# eVV_Sensors.net
KiCad netlist of a schematic drawn in Altium Designer
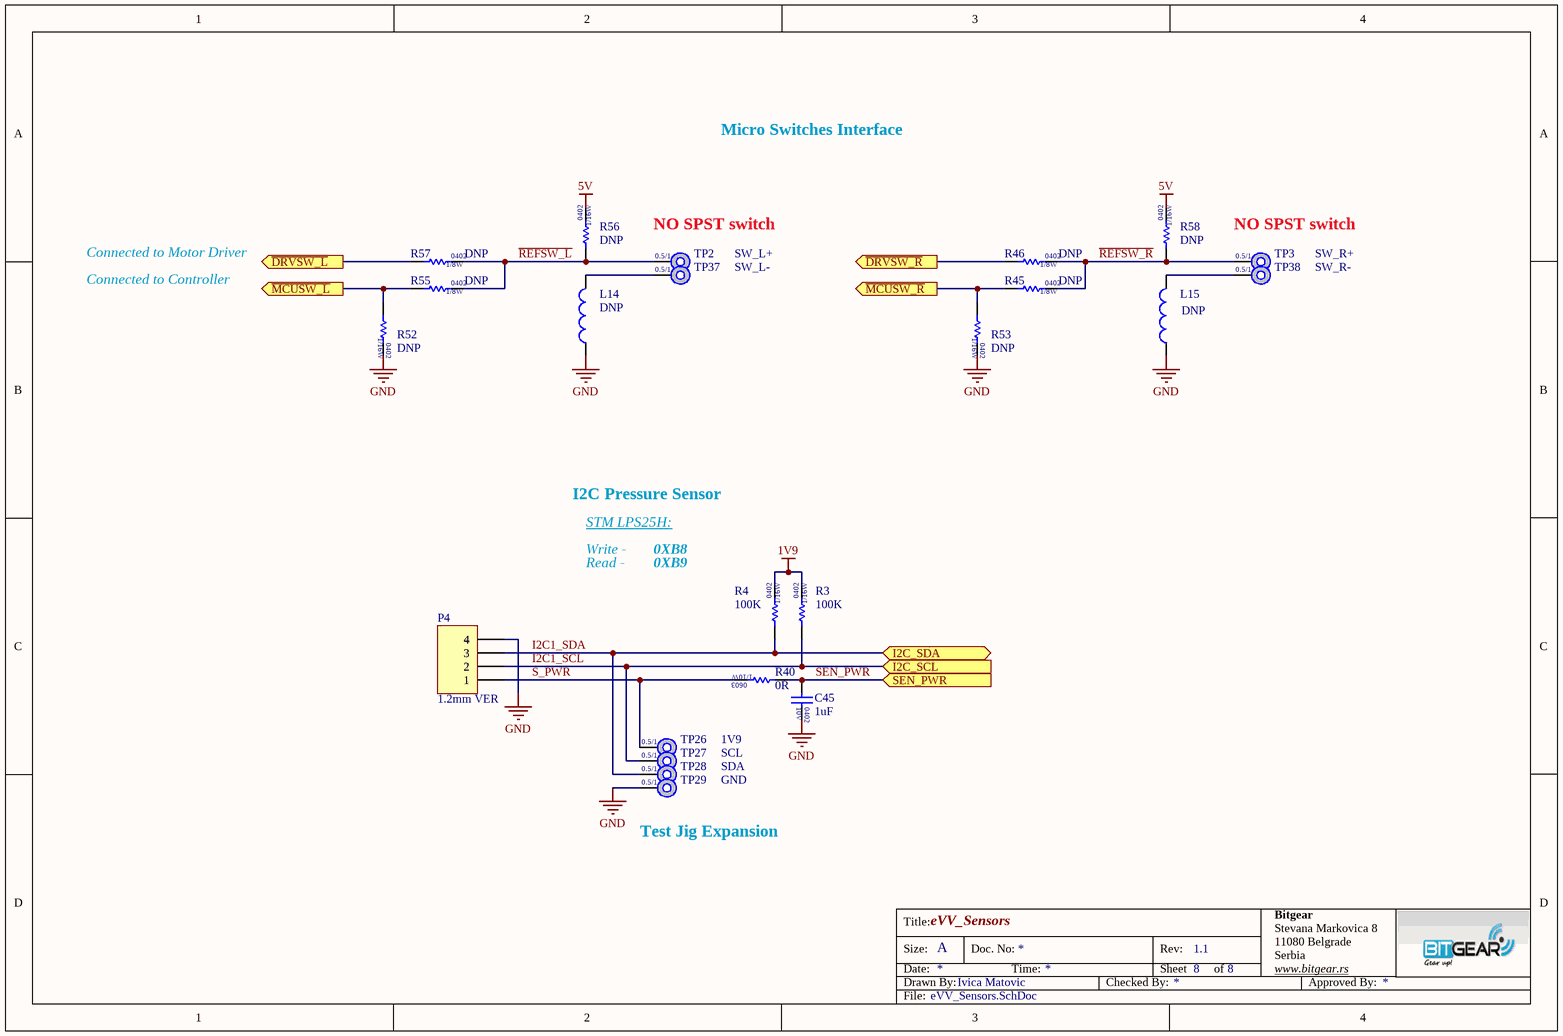
[diagram p0: eVV_Sensors.SchDoc]

(export (version "E")
  (design (tool "Eeschema 10.0.6"))
  (components
    (comp (ref "C45")
      (value "1uF")
      (footprint "CAPC1005X60N")
      (description "Cap-1005 (0402) CER 1uF 10V X5R 10%")
      (fields (field (name "MANUFACTURER") "Murata Electronics North America"))
      (libsource (lib "ecoVENTV") (part "Cap-1005 (0402) CER 1uF 10V X5R 10%"))
    )
    (comp (ref "L14")
      (value "DNP")
      (footprint "INDC1005X60N")
      (description "FERRITE BEAD 220 Ohm 800mA 0402")
      (fields (field (name "MANUFACTURER") "Taiyo Yuden"))
      (libsource (lib "ecoVENTV") (part "FBead-1005 (0402) 220 Ohm 800mA"))
    )
    (comp (ref "L15")
      (value "DNP")
      (footprint "INDC1005X60N")
      (description "FERRITE BEAD 220 Ohm 800mA 0402")
      (fields (field (name "MANUFACTURER") "Taiyo Yuden"))
      (libsource (lib "ecoVENTV") (part "FBead-1005 (0402) 220 Ohm 800mA"))
    )
    (comp (ref "P4")
      (value "1.2mm VER")
      (footprint "MOLEX_0781710004")
      (description "1.2mm pitch Pico-EZmate, Wire to Board, Vertical, with Locks, 1X4")
      (fields (field (name "MANUFACTURER") "Molex"))
      (libsource (lib "ecoVENTV") (part "Connector MOLEX Pico-EZmate 1X4 1.2mm"))
    )
    (comp (ref "R3")
      (value "100K")
      (footprint "RESC1005X40AN")
      (description "Res-1005 (0402) 100 KOhm 1/16W 1%")
      (fields (field (name "MANUFACTURER") "Vishay Dale"))
      (libsource (lib "ecoVENTV") (part "Res-1005 (0402) 100 KOhm 1/16W 1%"))
    )
    (comp (ref "R4")
      (value "100K")
      (footprint "RESC1005X40AN")
      (description "Res-1005 (0402) 100 KOhm 1/16W 1%")
      (fields (field (name "MANUFACTURER") "Vishay Dale"))
      (libsource (lib "ecoVENTV") (part "Res-1005 (0402) 100 KOhm 1/16W 1%"))
    )
    (comp (ref "R40")
      (value "0R")
      (footprint "RESC1608X84N")
      (description "Res-1608 (0603) 0 Ohm 1/10W")
      (fields (field (name "MANUFACTURER") "Samsung Electro-Mechanics America"))
      (libsource (lib "ecoVENTV") (part "Res-1608 (0603) 0 Ohm 1/10W"))
    )
    (comp (ref "R45")
      (value "DNP")
      (footprint "RESC1005X40AN")
      (description "Res-1005 (0402) 22 Ohm 1/8W 1%")
      (fields (field (name "MANUFACTURER") "Vishay Dale"))
      (libsource (lib "ecoVENTV") (part "Res-1005 (0402) 22 Ohm 1/8W 1%"))
    )
    (comp (ref "R46")
      (value "DNP")
      (footprint "RESC1005X40AN")
      (description "Res-1005 (0402) 22 Ohm 1/8W 1%")
      (fields (field (name "MANUFACTURER") "Vishay Dale"))
      (libsource (lib "ecoVENTV") (part "Res-1005 (0402) 22 Ohm 1/8W 1%"))
    )
    (comp (ref "R52")
      (value "DNP")
      (footprint "RESC1005X40AN")
      (description "Res-1005 (0402) 49.9 KOhm 1/16W 1%")
      (fields (field (name "MANUFACTURER") "Yageo"))
      (libsource (lib "ecoVENTV") (part "Res-1005 (0402) 49.9 KOhm 1/16W 1%"))
    )
    (comp (ref "R53")
      (value "DNP")
      (footprint "RESC1005X40AN")
      (description "Res-1005 (0402) 49.9 KOhm 1/16W 1%")
      (fields (field (name "MANUFACTURER") "Yageo"))
      (libsource (lib "ecoVENTV") (part "Res-1005 (0402) 49.9 KOhm 1/16W 1%"))
    )
    (comp (ref "R55")
      (value "DNP")
      (footprint "RESC1005X40AN")
      (description "Res-1005 (0402) 22 Ohm 1/8W 1%")
      (fields (field (name "MANUFACTURER") "Vishay Dale"))
      (libsource (lib "ecoVENTV") (part "Res-1005 (0402) 22 Ohm 1/8W 1%"))
    )
    (comp (ref "R56")
      (value "DNP")
      (footprint "RESC1005X40AN")
      (description "Res-1005 (0402) 100 KOhm 1/16W 1%")
      (fields (field (name "MANUFACTURER") "Vishay Dale"))
      (libsource (lib "ecoVENTV") (part "Res-1005 (0402) 100 KOhm 1/16W 1%"))
    )
    (comp (ref "R57")
      (value "DNP")
      (footprint "RESC1005X40AN")
      (description "Res-1005 (0402) 22 Ohm 1/8W 1%")
      (fields (field (name "MANUFACTURER") "Vishay Dale"))
      (libsource (lib "ecoVENTV") (part "Res-1005 (0402) 22 Ohm 1/8W 1%"))
    )
    (comp (ref "R58")
      (value "DNP")
      (footprint "RESC1005X40AN")
      (description "Res-1005 (0402) 100 KOhm 1/16W 1%")
      (fields (field (name "MANUFACTURER") "Vishay Dale"))
      (libsource (lib "ecoVENTV") (part "Res-1005 (0402) 100 KOhm 1/16W 1%"))
    )
    (comp (ref "TP2")
      (value "SW_L+")
      (footprint "TEST_POINT_TH_1MM")
      (description "Test point Through Hole")
      (libsource (lib "ecoVENTV") (part "TP TH"))
    )
    (comp (ref "TP3")
      (value "SW_R+")
      (footprint "TEST_POINT_TH_1MM")
      (description "Test point Through Hole")
      (libsource (lib "ecoVENTV") (part "TP TH"))
    )
    (comp (ref "TP26")
      (value "1V9")
      (footprint "TEST_POINT_TH_1MM")
      (description "Test point Through Hole")
      (libsource (lib "ecoVENTV") (part "TP TH"))
    )
    (comp (ref "TP27")
      (value "SCL")
      (footprint "TEST_POINT_TH_1MM")
      (description "Test point Through Hole")
      (libsource (lib "ecoVENTV") (part "TP TH"))
    )
    (comp (ref "TP28")
      (value "SDA")
      (footprint "TEST_POINT_TH_1MM")
      (description "Test point Through Hole")
      (libsource (lib "ecoVENTV") (part "TP TH"))
    )
    (comp (ref "TP29")
      (value "GND")
      (footprint "TEST_POINT_TH_1MM")
      (description "Test point Through Hole")
      (libsource (lib "ecoVENTV") (part "TP TH"))
    )
    (comp (ref "TP37")
      (value "SW_L-")
      (footprint "TEST_POINT_TH_1MM")
      (description "Test point Through Hole")
      (libsource (lib "ecoVENTV") (part "TP TH"))
    )
    (comp (ref "TP38")
      (value "SW_R-")
      (footprint "TEST_POINT_TH_1MM")
      (description "Test point Through Hole")
      (libsource (lib "ecoVENTV") (part "TP TH"))
    )
  )
  (nets
    (net (code "1") (name "/DRVSW_L") (class "Default")
      (node (ref "R57") (pin "2") (pinfunction "2_2") (pintype "passive"))
    )
    (net (code "2") (name "/DRVSW_R") (class "Default")
      (node (ref "R46") (pin "2") (pinfunction "2_2") (pintype "passive"))
    )
    (net (code "3") (name "/I2C1_SCL") (class "Default")
      (node (ref "P4") (pin "2") (pinfunction "2_2") (pintype "passive"))
      (node (ref "R3") (pin "2") (pinfunction "2_2") (pintype "passive"))
      (node (ref "TP27") (pin "1") (pinfunction "1_1") (pintype "passive"))
    )
    (net (code "4") (name "/I2C1_SDA") (class "Default")
      (node (ref "P4") (pin "3") (pinfunction "3_3") (pintype "passive"))
      (node (ref "R4") (pin "2") (pinfunction "2_2") (pintype "passive"))
      (node (ref "TP28") (pin "1") (pinfunction "1_1") (pintype "passive"))
    )
    (net (code "5") (name "/MCUSW_L") (class "Default")
      (node (ref "R52") (pin "2") (pinfunction "2_2") (pintype "passive"))
      (node (ref "R55") (pin "2") (pinfunction "2_2") (pintype "passive"))
    )
    (net (code "6") (name "/MCUSW_R") (class "Default")
      (node (ref "R45") (pin "2") (pinfunction "2_2") (pintype "passive"))
      (node (ref "R53") (pin "2") (pinfunction "2_2") (pintype "passive"))
    )
    (net (code "7") (name "/REFSW_L") (class "Default")
      (node (ref "R55") (pin "1") (pinfunction "1_1") (pintype "passive"))
      (node (ref "R56") (pin "2") (pinfunction "2_2") (pintype "passive"))
      (node (ref "R57") (pin "1") (pinfunction "1_1") (pintype "passive"))
      (node (ref "TP2") (pin "1") (pinfunction "1_1") (pintype "passive"))
    )
    (net (code "8") (name "/REFSW_R") (class "Default")
      (node (ref "R45") (pin "1") (pinfunction "1_1") (pintype "passive"))
      (node (ref "R46") (pin "1") (pinfunction "1_1") (pintype "passive"))
      (node (ref "R58") (pin "2") (pinfunction "2_2") (pintype "passive"))
      (node (ref "TP3") (pin "1") (pinfunction "1_1") (pintype "passive"))
    )
    (net (code "9") (name "/SEN_PWR") (class "Default")
      (node (ref "C45") (pin "1") (pinfunction "1_1") (pintype "passive"))
      (node (ref "R40") (pin "2") (pinfunction "2_2") (pintype "passive"))
    )
    (net (code "10") (name "/S_PWR") (class "Default")
      (node (ref "P4") (pin "1") (pinfunction "1_1") (pintype "passive"))
      (node (ref "R40") (pin "1") (pinfunction "1_1") (pintype "passive"))
      (node (ref "TP26") (pin "1") (pinfunction "1_1") (pintype "passive"))
    )
    (net (code "11") (name "1V9") (class "Default")
      (node (ref "R3") (pin "1") (pinfunction "1_1") (pintype "passive"))
      (node (ref "R4") (pin "1") (pinfunction "1_1") (pintype "passive"))
    )
    (net (code "12") (name "5V") (class "Default")
      (node (ref "R56") (pin "1") (pinfunction "1_1") (pintype "passive"))
      (node (ref "R58") (pin "1") (pinfunction "1_1") (pintype "passive"))
    )
    (net (code "13") (name "GND") (class "Default")
      (node (ref "C45") (pin "2") (pinfunction "2_2") (pintype "passive"))
      (node (ref "L14") (pin "1") (pinfunction "1_1") (pintype "passive"))
      (node (ref "L15") (pin "1") (pinfunction "1_1") (pintype "passive"))
      (node (ref "P4") (pin "4") (pinfunction "4_4") (pintype "passive"))
      (node (ref "R52") (pin "1") (pinfunction "1_1") (pintype "passive"))
      (node (ref "R53") (pin "1") (pinfunction "1_1") (pintype "passive"))
      (node (ref "TP29") (pin "1") (pinfunction "1_1") (pintype "passive"))
    )
    (net (code "14") (name "Net-(L14-Pad2)") (class "Default")
      (node (ref "L14") (pin "2") (pinfunction "2_2") (pintype "passive"))
      (node (ref "TP37") (pin "1") (pinfunction "1_1") (pintype "passive"))
    )
    (net (code "15") (name "Net-(L15-Pad2)") (class "Default")
      (node (ref "L15") (pin "2") (pinfunction "2_2") (pintype "passive"))
      (node (ref "TP38") (pin "1") (pinfunction "1_1") (pintype "passive"))
    )
  )
)
